# Connectors.net
KiCad netlist of a schematic drawn in Altium Designer
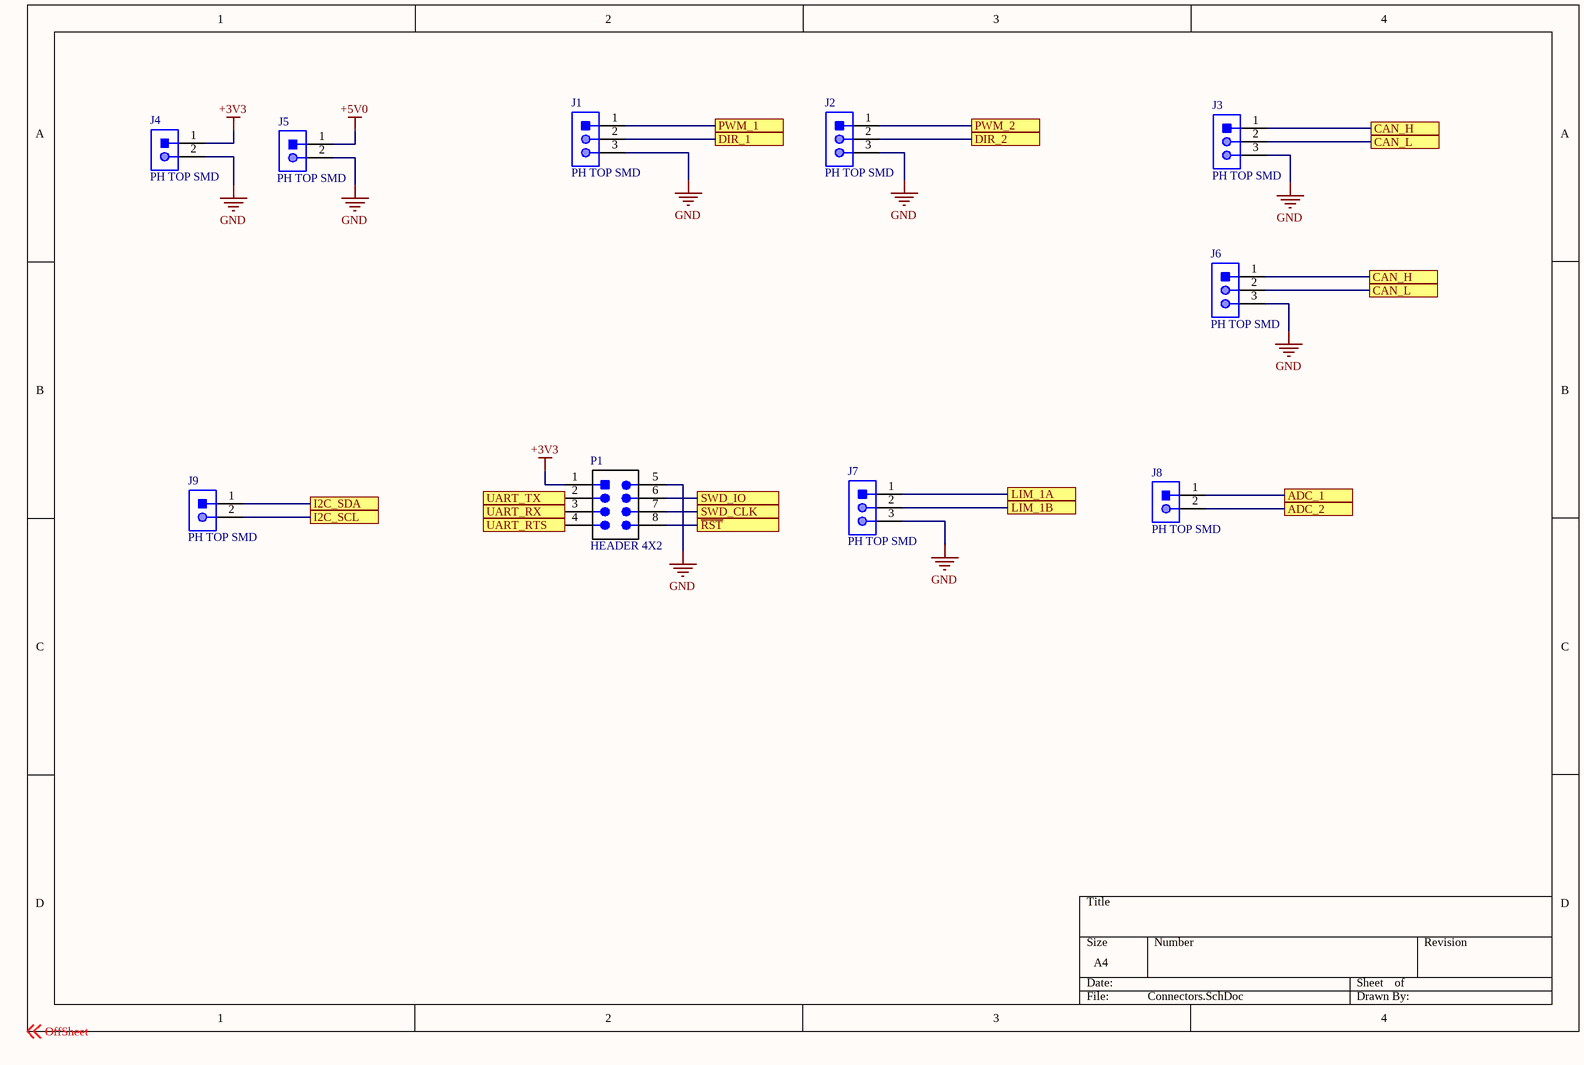
[diagram p0: Connectors.SchDoc]

(export (version "E")
  (design (tool "Eeschema 10.0.6"))
  (components
    (comp (ref "J1")
      (value "PH TOP SMD")
      (footprint "JST-B3B-SM4-TB")
      (description "CONN HEADER PH TOP 3POS 2MM SMD")
      (fields (field (name "MANUFACTURER") "JST") (field (name "PART NUMBER") "B3B-PH-SM4-TB"))
      (libsource (lib "UWRT_Schematic_Library_2019") (part "CON_3M_PH_TOP_SMT"))
    )
    (comp (ref "J2")
      (value "PH TOP SMD")
      (footprint "JST-B3B-SM4-TB")
      (description "CONN HEADER PH TOP 3POS 2MM SMD")
      (fields (field (name "MANUFACTURER") "JST") (field (name "PART NUMBER") "B3B-PH-SM4-TB"))
      (libsource (lib "UWRT_Schematic_Library_2019") (part "CON_3M_PH_TOP_SMT"))
    )
    (comp (ref "J3")
      (value "PH TOP SMD")
      (footprint "JST-B3B-SM4-TB")
      (description "CONN HEADER PH TOP 3POS 2MM SMD")
      (fields (field (name "MANUFACTURER") "JST") (field (name "PART NUMBER") "B3B-PH-SM4-TB"))
      (libsource (lib "UWRT_Schematic_Library_2019") (part "CON_3M_PH_TOP_SMT"))
    )
    (comp (ref "J4")
      (value "PH TOP SMD")
      (footprint "JST-B2B-SM4-TB")
      (description "CONN HEADER PH TOP 2POS 2MM SMD")
      (fields (field (name "MANUFACTURER") "JST") (field (name "PART NUMBER") "B2B-PH-SM4-TB"))
      (libsource (lib "UWRT_Schematic_Library_2019") (part "CON_2M_PH_TOP_SMT"))
    )
    (comp (ref "J5")
      (value "PH TOP SMD")
      (footprint "JST-B2B-SM4-TB")
      (description "CONN HEADER PH TOP 2POS 2MM SMD")
      (fields (field (name "MANUFACTURER") "JST") (field (name "PART NUMBER") "B2B-PH-SM4-TB"))
      (libsource (lib "UWRT_Schematic_Library_2019") (part "CON_2M_PH_TOP_SMT"))
    )
    (comp (ref "J6")
      (value "PH TOP SMD")
      (footprint "JST-B3B-SM4-TB")
      (description "CONN HEADER PH TOP 3POS 2MM SMD")
      (fields (field (name "MANUFACTURER") "JST") (field (name "PART NUMBER") "B3B-PH-SM4-TB"))
      (libsource (lib "UWRT_Schematic_Library_2019") (part "CON_3M_PH_TOP_SMT"))
    )
    (comp (ref "J7")
      (value "PH TOP SMD")
      (footprint "JST-B3B-SM4-TB")
      (description "CONN HEADER PH TOP 3POS 2MM SMD")
      (fields (field (name "MANUFACTURER") "JST") (field (name "PART NUMBER") "B3B-PH-SM4-TB"))
      (libsource (lib "UWRT_Schematic_Library_2019") (part "CON_3M_PH_TOP_SMT"))
    )
    (comp (ref "J8")
      (value "PH TOP SMD")
      (footprint "JST-B2B-SM4-TB")
      (description "CONN HEADER PH TOP 2POS 2MM SMD")
      (fields (field (name "MANUFACTURER") "JST") (field (name "PART NUMBER") "B2B-PH-SM4-TB"))
      (libsource (lib "UWRT_Schematic_Library_2019") (part "CON_2M_PH_TOP_SMT"))
    )
    (comp (ref "J9")
      (value "PH TOP SMD")
      (footprint "JST-B2B-SM4-TB")
      (description "CONN HEADER PH TOP 2POS 2MM SMD")
      (fields (field (name "MANUFACTURER") "JST") (field (name "PART NUMBER") "B2B-PH-SM4-TB"))
      (libsource (lib "UWRT_Schematic_Library_2019") (part "CON_2M_PH_TOP_SMT"))
    )
    (comp (ref "P1")
      (value "HEADER 4X2")
      (footprint "UWRT_Footprint_Library_2019:HEADER_2X4")
      (description "Header, 4-Pin Dual row")
      (fields (field (name "PUBLISHER") "Altium Limited"))
      (libsource (lib "UWRT_Schematic_Library_2019") (part "HEADER 4X2"))
    )
  )
  (nets
    (net (code "1") (name "+3V3") (class "Default")
      (node (ref "J4") (pin "1") (pinfunction "1_1") (pintype "passive"))
      (node (ref "P1") (pin "1") (pinfunction "VCC_1") (pintype "passive"))
    )
    (net (code "2") (name "+5V0") (class "Default")
      (node (ref "J5") (pin "1") (pinfunction "1_1") (pintype "passive"))
    )
    (net (code "3") (name "/ADC_1") (class "Default")
      (node (ref "J8") (pin "1") (pinfunction "1_1") (pintype "passive"))
    )
    (net (code "4") (name "/ADC_2") (class "Default")
      (node (ref "J8") (pin "2") (pinfunction "2_2") (pintype "passive"))
    )
    (net (code "5") (name "/CAN_H") (class "Default")
      (node (ref "J3") (pin "1") (pinfunction "1_1") (pintype "passive"))
      (node (ref "J6") (pin "1") (pinfunction "1_1") (pintype "passive"))
    )
    (net (code "6") (name "/CAN_L") (class "Default")
      (node (ref "J3") (pin "2") (pinfunction "2_2") (pintype "passive"))
      (node (ref "J6") (pin "2") (pinfunction "2_2") (pintype "passive"))
    )
    (net (code "7") (name "/DIR_1") (class "Default")
      (node (ref "J1") (pin "2") (pinfunction "2_2") (pintype "passive"))
    )
    (net (code "8") (name "/DIR_2") (class "Default")
      (node (ref "J2") (pin "2") (pinfunction "2_2") (pintype "passive"))
    )
    (net (code "9") (name "/I2C_SCL") (class "Default")
      (node (ref "J9") (pin "2") (pinfunction "2_2") (pintype "passive"))
    )
    (net (code "10") (name "/I2C_SDA") (class "Default")
      (node (ref "J9") (pin "1") (pinfunction "1_1") (pintype "passive"))
    )
    (net (code "11") (name "/LIM_1A") (class "Default")
      (node (ref "J7") (pin "1") (pinfunction "1_1") (pintype "passive"))
    )
    (net (code "12") (name "/LIM_1B") (class "Default")
      (node (ref "J7") (pin "2") (pinfunction "2_2") (pintype "passive"))
    )
    (net (code "13") (name "/PWM_1") (class "Default")
      (node (ref "J1") (pin "1") (pinfunction "1_1") (pintype "passive"))
    )
    (net (code "14") (name "/PWM_2") (class "Default")
      (node (ref "J2") (pin "1") (pinfunction "1_1") (pintype "passive"))
    )
    (net (code "15") (name "/SWD_CLK") (class "Default")
      (node (ref "P1") (pin "7") (pinfunction "3_7") (pintype "passive"))
    )
    (net (code "16") (name "/SWD_IO") (class "Default")
      (node (ref "P1") (pin "6") (pinfunction "2_6") (pintype "passive"))
    )
    (net (code "17") (name "/UART_RTS") (class "Default")
      (node (ref "P1") (pin "4") (pinfunction "4_4") (pintype "passive"))
    )
    (net (code "18") (name "/UART_RX") (class "Default")
      (node (ref "P1") (pin "3") (pinfunction "3_3") (pintype "passive"))
    )
    (net (code "19") (name "/UART_TX") (class "Default")
      (node (ref "P1") (pin "2") (pinfunction "2_2") (pintype "passive"))
    )
    (net (code "20") (name "/~{RST}") (class "Default")
      (node (ref "P1") (pin "8") (pinfunction "4_8") (pintype "passive"))
    )
    (net (code "21") (name "GND") (class "Default")
      (node (ref "J1") (pin "3") (pinfunction "3_3") (pintype "passive"))
      (node (ref "J2") (pin "3") (pinfunction "3_3") (pintype "passive"))
      (node (ref "J3") (pin "3") (pinfunction "3_3") (pintype "passive"))
      (node (ref "J4") (pin "2") (pinfunction "2_2") (pintype "passive"))
      (node (ref "J5") (pin "2") (pinfunction "2_2") (pintype "passive"))
      (node (ref "J6") (pin "3") (pinfunction "3_3") (pintype "passive"))
      (node (ref "J7") (pin "3") (pinfunction "3_3") (pintype "passive"))
      (node (ref "P1") (pin "5") (pinfunction "GND_5") (pintype "passive"))
    )
  )
)
